# SparkFun_MicroMod_Function_ADIN1110.net
KiCad netlist of a schematic drawn in EAGLE
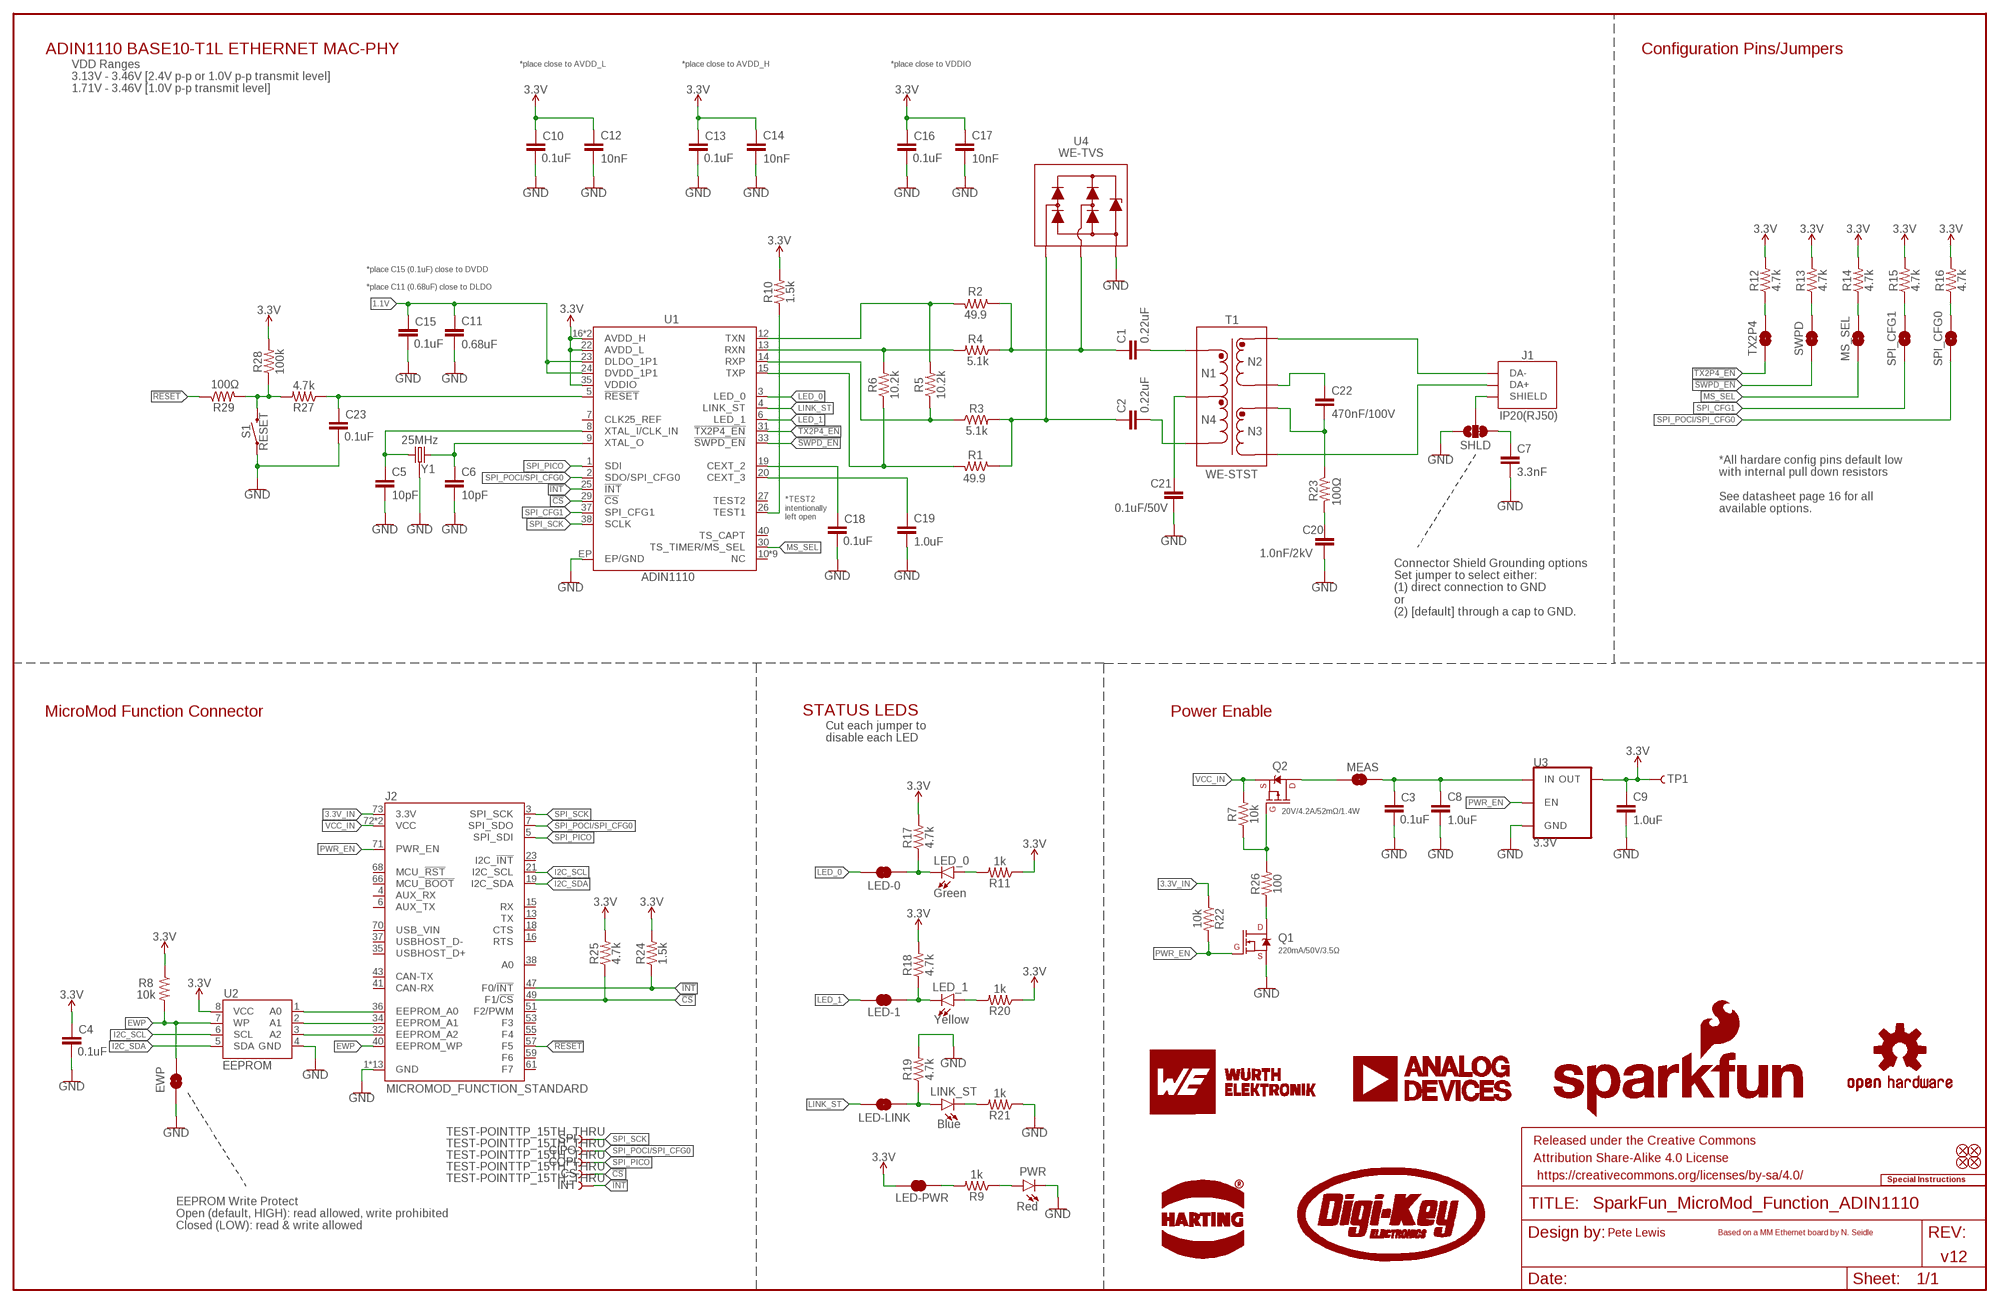
[diagram p0: schematic, sheet 1]

(export (version "E")
  (design (tool "Eeschema 10.0.6"))
  (components
    (comp (ref "C1")
      (value "0.22uF")
      (footprint "eagle-import:0603")
      (libsource (lib "eagle-import") (part "0.22UF-0603-50V-10%"))
    )
    (comp (ref "C2")
      (value "0.22uF")
      (footprint "eagle-import:0603")
      (libsource (lib "eagle-import") (part "0.22UF-0603-50V-10%"))
    )
    (comp (ref "C3")
      (value "0.1uF")
      (footprint "eagle-import:0603")
      (libsource (lib "eagle-import") (part "0.1UF-0603-25V-10%-X7R-WE"))
    )
    (comp (ref "C4")
      (value "0.1uF")
      (footprint "eagle-import:0603")
      (libsource (lib "eagle-import") (part "0.1UF-0603-25V-10%-X7R-WE"))
    )
    (comp (ref "C5")
      (value "10pF")
      (footprint "eagle-import:0603")
      (libsource (lib "eagle-import") (part "10PF-0603-50V-5%-C0G-WE"))
    )
    (comp (ref "C6")
      (value "10pF")
      (footprint "eagle-import:0603")
      (libsource (lib "eagle-import") (part "10PF-0603-50V-5%-C0G-WE"))
    )
    (comp (ref "C7")
      (value "3.3nF")
      (footprint "eagle-import:0603")
      (libsource (lib "eagle-import") (part "3.3NF-0603-100V-10%-WE"))
    )
    (comp (ref "C8")
      (value "1.0uF")
      (footprint "eagle-import:0603")
      (libsource (lib "eagle-import") (part "1.0UF-0603-16V-10%-X7R-WE"))
    )
    (comp (ref "C9")
      (value "1.0uF")
      (footprint "eagle-import:0603")
      (libsource (lib "eagle-import") (part "1.0UF-0603-16V-10%-X7R-WE"))
    )
    (comp (ref "C10")
      (value "0.1uF")
      (footprint "eagle-import:0402-TIGHT")
      (libsource (lib "eagle-import") (part "0.1UF-0402T-16V-10%-X7R-WE"))
    )
    (comp (ref "C11")
      (value "0.68uF")
      (footprint "eagle-import:0603")
      (libsource (lib "eagle-import") (part "0.68UF-0603-16V-10%-X7R-WE"))
    )
    (comp (ref "C12")
      (value "10nF")
      (footprint "eagle-import:0402-TIGHT")
      (libsource (lib "eagle-import") (part "10NF-0402T-25V-10%-X7R-WE"))
    )
    (comp (ref "C13")
      (value "0.1uF")
      (footprint "eagle-import:0402-TIGHT")
      (libsource (lib "eagle-import") (part "0.1UF-0402T-16V-10%-X7R-WE"))
    )
    (comp (ref "C14")
      (value "10nF")
      (footprint "eagle-import:0402-TIGHT")
      (libsource (lib "eagle-import") (part "10NF-0402T-25V-10%-X7R-WE"))
    )
    (comp (ref "C15")
      (value "0.1uF")
      (footprint "eagle-import:0402-TIGHT")
      (libsource (lib "eagle-import") (part "0.1UF-0402T-16V-10%-X7R-WE"))
    )
    (comp (ref "C16")
      (value "0.1uF")
      (footprint "eagle-import:0402-TIGHT")
      (libsource (lib "eagle-import") (part "0.1UF-0402T-16V-10%-X7R-WE"))
    )
    (comp (ref "C17")
      (value "10nF")
      (footprint "eagle-import:0402-TIGHT")
      (libsource (lib "eagle-import") (part "10NF-0402T-25V-10%-X7R-WE"))
    )
    (comp (ref "C18")
      (value "0.1uF")
      (footprint "eagle-import:0402-TIGHT")
      (libsource (lib "eagle-import") (part "0.1UF-0402T-16V-10%-X7R-WE"))
    )
    (comp (ref "C19")
      (value "1.0uF")
      (footprint "eagle-import:0402-TIGHT")
      (libsource (lib "eagle-import") (part "1.0UF-0402T-16V-10%"))
    )
    (comp (ref "C20")
      (value "1.0nF/2kV")
      (footprint "eagle-import:1206")
      (libsource (lib "eagle-import") (part "1.0NF/1000PF-1206-2KV-10%-X7R-WORTH-ELEKRONIK"))
    )
    (comp (ref "C21")
      (value "0.1uF/50V")
      (footprint "eagle-import:0603")
      (libsource (lib "eagle-import") (part "0.1UF-0603-50V-10%-X7R-WE"))
    )
    (comp (ref "C22")
      (value "470nF/100V")
      (footprint "eagle-import:0805")
      (libsource (lib "eagle-import") (part "470NF-0805-100V-10%-X7S"))
    )
    (comp (ref "C23")
      (value "0.1uF")
      (footprint "eagle-import:0402-TIGHT")
      (libsource (lib "eagle-import") (part "0.1UF-0402T-16V-10%-X7R-WE"))
    )
    (comp (ref "CIPO")
      (value "TEST-POINTTP_15TH_THRU")
      (footprint "eagle-import:TP_15TH")
      (libsource (lib "eagle-import") (part "TEST-POINTTP_15TH_THRU"))
    )
    (comp (ref "COPI")
      (value "TEST-POINTTP_15TH_THRU")
      (footprint "eagle-import:TP_15TH")
      (libsource (lib "eagle-import") (part "TEST-POINTTP_15TH_THRU"))
    )
    (comp (ref "CS")
      (value "TEST-POINTTP_15TH_THRU")
      (footprint "eagle-import:TP_15TH")
      (libsource (lib "eagle-import") (part "TEST-POINTTP_15TH_THRU"))
    )
    (comp (ref "EWP")
      (value "JUMPER-SMT_2_NO_SILK")
      (footprint "eagle-import:SMT-JUMPER_2_NO_SILK")
      (libsource (lib "eagle-import") (part "JUMPER-SMT_2_NO_SILK"))
    )
    (comp (ref "FD1")
      (value "FIDUCIALUFIDUCIAL")
      (footprint "eagle-import:FIDUCIAL-MICRO")
      (libsource (lib "eagle-import") (part "FIDUCIALUFIDUCIAL"))
    )
    (comp (ref "FD2")
      (value "FIDUCIALUFIDUCIAL")
      (footprint "eagle-import:FIDUCIAL-MICRO")
      (libsource (lib "eagle-import") (part "FIDUCIALUFIDUCIAL"))
    )
    (comp (ref "FD3")
      (value "FIDUCIALUFIDUCIAL")
      (footprint "eagle-import:FIDUCIAL-MICRO")
      (libsource (lib "eagle-import") (part "FIDUCIALUFIDUCIAL"))
    )
    (comp (ref "FD4")
      (value "FIDUCIALUFIDUCIAL")
      (footprint "eagle-import:FIDUCIAL-MICRO")
      (libsource (lib "eagle-import") (part "FIDUCIALUFIDUCIAL"))
    )
    (comp (ref "FRAME1")
      (value "FRAME-LEDGER")
      (footprint "eagle-import:CREATIVE_COMMONS")
      (libsource (lib "eagle-import") (part "FRAME-LEDGER"))
    )
    (comp (ref "INT")
      (value "TEST-POINTTP_15TH_THRU")
      (footprint "eagle-import:TP_15TH")
      (libsource (lib "eagle-import") (part "TEST-POINTTP_15TH_THRU"))
    )
    (comp (ref "J1")
      (value "IP20(RJ50)")
      (footprint "eagle-import:T1_INDUSTRIAL_JACK_AH_IP20")
      (libsource (lib "eagle-import") (part "T1_INDUSTRIAL_JACK_AH_IP20"))
    )
    (comp (ref "J2")
      (value "MICROMOD_FUNCTION_STANDARD")
      (footprint "eagle-import:M.2-CARD-E-22_FUNCTION_STANDARD")
      (libsource (lib "eagle-import") (part "MICROMOD_FUNCTION_STANDARD"))
    )
    (comp (ref "LED-0")
      (value "JUMPER-SMT_2_NC_TRACE_SILK")
      (footprint "eagle-import:SMT-JUMPER_2_NC_TRACE_SILK")
      (libsource (lib "eagle-import") (part "JUMPER-SMT_2_NC_TRACE_SILK"))
    )
    (comp (ref "LED-1")
      (value "JUMPER-SMT_2_NC_TRACE_SILK")
      (footprint "eagle-import:SMT-JUMPER_2_NC_TRACE_SILK")
      (libsource (lib "eagle-import") (part "JUMPER-SMT_2_NC_TRACE_SILK"))
    )
    (comp (ref "LED-LINK")
      (value "JUMPER-SMT_2_NC_TRACE_SILK")
      (footprint "eagle-import:SMT-JUMPER_2_NC_TRACE_SILK")
      (libsource (lib "eagle-import") (part "JUMPER-SMT_2_NC_TRACE_SILK"))
    )
    (comp (ref "LED-PWR")
      (value "JUMPER-SMT_2_NC_TRACE_SILK")
      (footprint "eagle-import:SMT-JUMPER_2_NC_TRACE_SILK")
      (libsource (lib "eagle-import") (part "JUMPER-SMT_2_NC_TRACE_SILK"))
    )
    (comp (ref "LED_0")
      (value "Green")
      (footprint "eagle-import:LED-0603")
      (libsource (lib "eagle-import") (part "LED-GREEN-0603-WE"))
    )
    (comp (ref "LED_1")
      (value "Yellow")
      (footprint "eagle-import:LED-0603")
      (libsource (lib "eagle-import") (part "LED-YELLOW-0603-WE"))
    )
    (comp (ref "LINK_ST")
      (value "Blue")
      (footprint "eagle-import:LED-0603")
      (libsource (lib "eagle-import") (part "LED-BLUE-0603-WE"))
    )
    (comp (ref "LOGO1")
      (value "SFE_LOGO_NAME_FLAME.1_INCH")
      (footprint "eagle-import:SFE_LOGO_NAME_FLAME_.1")
      (libsource (lib "eagle-import") (part "SFE_LOGO_NAME_FLAME.1_INCH"))
    )
    (comp (ref "LOGO2")
      (value "SPECIAL_INSTRUCTIONS-ORDERING")
      (footprint "eagle-import:ORDERING_INSTRUCTIONS")
      (libsource (lib "eagle-import") (part "SPECIAL_INSTRUCTIONS-ORDERING"))
    )
    (comp (ref "LOGO3")
      (value "OSHW-LOGOMINI")
      (footprint "eagle-import:OSHW-LOGO-MINI")
      (libsource (lib "eagle-import") (part "OSHW-LOGOMINI"))
    )
    (comp (ref "MEAS")
      (value "JUMPER-COMBO_2_NC_TRACE")
      (footprint "eagle-import:COMBO-JUMPER_2_NC_TRACE")
      (libsource (lib "eagle-import") (part "JUMPER-COMBO_2_NC_TRACE"))
    )
    (comp (ref "MS_SEL")
      (value "JUMPER-SMT_2_NO_SILK")
      (footprint "eagle-import:SMT-JUMPER_2_NO_SILK")
      (libsource (lib "eagle-import") (part "JUMPER-SMT_2_NO_SILK"))
    )
    (comp (ref "PWR")
      (value "Red")
      (footprint "eagle-import:LED-0603")
      (libsource (lib "eagle-import") (part "LED-RED-0603-WE"))
    )
    (comp (ref "Q1")
      (value "220mA/50V/3.5Ω")
      (footprint "eagle-import:SOT23-3")
      (libsource (lib "eagle-import") (part "MOSFET-NCH-BSS138"))
    )
    (comp (ref "Q2")
      (value "20V/4.2A/52mΩ/1.4W")
      (footprint "eagle-import:SOT23-3")
      (libsource (lib "eagle-import") (part "MOSFET_PCH-DMG2305UX-7"))
    )
    (comp (ref "R1")
      (value "49.9")
      (footprint "eagle-import:0603")
      (libsource (lib "eagle-import") (part "49.9OHM-0603-1/10W-1%"))
    )
    (comp (ref "R2")
      (value "49.9")
      (footprint "eagle-import:0603")
      (libsource (lib "eagle-import") (part "49.9OHM-0603-1/10W-1%"))
    )
    (comp (ref "R3")
      (value "5.1k")
      (footprint "eagle-import:0402-TIGHT")
      (libsource (lib "eagle-import") (part "5.1KOHM-0402T-1/16W-1%"))
    )
    (comp (ref "R4")
      (value "5.1k")
      (footprint "eagle-import:0402-TIGHT")
      (libsource (lib "eagle-import") (part "5.1KOHM-0402T-1/16W-1%"))
    )
    (comp (ref "R5")
      (value "10.2k")
      (footprint "eagle-import:0402-TIGHT")
      (libsource (lib "eagle-import") (part "10.2KOHM-0402-1/16W-1%"))
    )
    (comp (ref "R6")
      (value "10.2k")
      (footprint "eagle-import:0402-TIGHT")
      (libsource (lib "eagle-import") (part "10.2KOHM-0402-1/16W-1%"))
    )
    (comp (ref "R7")
      (value "10k")
      (footprint "eagle-import:0603")
      (libsource (lib "eagle-import") (part "10KOHM-0603-1/10W-1%"))
    )
    (comp (ref "R8")
      (value "10k")
      (footprint "eagle-import:0603")
      (libsource (lib "eagle-import") (part "10KOHM-0603-1/10W-1%"))
    )
    (comp (ref "R9")
      (value "1k")
      (footprint "eagle-import:0402-TIGHT")
      (libsource (lib "eagle-import") (part "1KOHM-0402T-1/16W-1%"))
    )
    (comp (ref "R10")
      (value "1.5k")
      (footprint "eagle-import:0603")
      (libsource (lib "eagle-import") (part "1.5KOHM-0603-1/10W-1%"))
    )
    (comp (ref "R11")
      (value "1k")
      (footprint "eagle-import:0402-TIGHT")
      (libsource (lib "eagle-import") (part "1KOHM-0402T-1/16W-1%"))
    )
    (comp (ref "R12")
      (value "4.7k")
      (footprint "eagle-import:0402-TIGHT")
      (libsource (lib "eagle-import") (part "4.7KOHM-0402T-1/16W-1%"))
    )
    (comp (ref "R13")
      (value "4.7k")
      (footprint "eagle-import:0402-TIGHT")
      (libsource (lib "eagle-import") (part "4.7KOHM-0402T-1/16W-1%"))
    )
    (comp (ref "R14")
      (value "4.7k")
      (footprint "eagle-import:0402-TIGHT")
      (libsource (lib "eagle-import") (part "4.7KOHM-0402T-1/16W-1%"))
    )
    (comp (ref "R15")
      (value "4.7k")
      (footprint "eagle-import:0402-TIGHT")
      (libsource (lib "eagle-import") (part "4.7KOHM-0402T-1/16W-1%"))
    )
    (comp (ref "R16")
      (value "4.7k")
      (footprint "eagle-import:0402-TIGHT")
      (libsource (lib "eagle-import") (part "4.7KOHM-0402T-1/16W-1%"))
    )
    (comp (ref "R17")
      (value "4.7k")
      (footprint "eagle-import:0402-TIGHT")
      (libsource (lib "eagle-import") (part "4.7KOHM-0402T-1/16W-1%"))
    )
    (comp (ref "R18")
      (value "4.7k")
      (footprint "eagle-import:0402-TIGHT")
      (libsource (lib "eagle-import") (part "4.7KOHM-0402T-1/16W-1%"))
    )
    (comp (ref "R19")
      (value "4.7k")
      (footprint "eagle-import:0402-TIGHT")
      (libsource (lib "eagle-import") (part "4.7KOHM-0402T-1/16W-1%"))
    )
    (comp (ref "R20")
      (value "1k")
      (footprint "eagle-import:0402-TIGHT")
      (libsource (lib "eagle-import") (part "1KOHM-0402T-1/16W-1%"))
    )
    (comp (ref "R21")
      (value "1k")
      (footprint "eagle-import:0402-TIGHT")
      (libsource (lib "eagle-import") (part "1KOHM-0402T-1/16W-1%"))
    )
    (comp (ref "R22")
      (value "10k")
      (footprint "eagle-import:0603")
      (libsource (lib "eagle-import") (part "10KOHM-0603-1/10W-1%"))
    )
    (comp (ref "R23")
      (value "100Ω")
      (footprint "eagle-import:0603")
      (libsource (lib "eagle-import") (part "100OHM-0603-1/10W-1%"))
    )
    (comp (ref "R24")
      (value "1.5k")
      (footprint "eagle-import:0603")
      (libsource (lib "eagle-import") (part "1.5KOHM-0603-1/10W-1%"))
    )
    (comp (ref "R25")
      (value "4.7k")
      (footprint "eagle-import:0402-TIGHT")
      (libsource (lib "eagle-import") (part "4.7KOHM-0402T-1/16W-1%"))
    )
    (comp (ref "R26")
      (value "100")
      (footprint "eagle-import:0603")
      (libsource (lib "eagle-import") (part "100OHM-0603-1/10W-1%"))
    )
    (comp (ref "R27")
      (value "4.7k")
      (footprint "eagle-import:0603")
      (libsource (lib "eagle-import") (part "4.7KOHM-0603-1/10W-1%"))
    )
    (comp (ref "R28")
      (value "100k")
      (footprint "eagle-import:0402-TIGHT")
      (libsource (lib "eagle-import") (part "100KOHM-0402T-1/16W-1%"))
    )
    (comp (ref "R29")
      (value "100Ω")
      (footprint "eagle-import:0603")
      (libsource (lib "eagle-import") (part "100OHM-0603-1/10W-1%"))
    )
    (comp (ref "S1")
      (value "RESET")
      (footprint "eagle-import:TACTILE_SWITCH_SMD_5.2MM")
      (libsource (lib "eagle-import") (part "MOMENTARY-SWITCH-SPST-SMD-5.2MM-TALL"))
    )
    (comp (ref "SHLD")
      (value "JUMPER-SMT_3_1-NC_TRACE_SILK")
      (footprint "eagle-import:SMT-JUMPER_3_1-NC_TRACE_SILK")
      (libsource (lib "eagle-import") (part "JUMPER-SMT_3_1-NC_TRACE_SILK"))
    )
    (comp (ref "SPI")
      (value "TEST-POINTTP_15TH_THRU")
      (footprint "eagle-import:TP_15TH")
      (libsource (lib "eagle-import") (part "TEST-POINTTP_15TH_THRU"))
    )
    (comp (ref "SPI_CFG0")
      (value "JUMPER-SMT_2_NO_SILK")
      (footprint "eagle-import:SMT-JUMPER_2_NO_SILK")
      (libsource (lib "eagle-import") (part "JUMPER-SMT_2_NO_SILK"))
    )
    (comp (ref "SPI_CFG1")
      (value "JUMPER-SMT_2_NO_SILK")
      (footprint "eagle-import:SMT-JUMPER_2_NO_SILK")
      (libsource (lib "eagle-import") (part "JUMPER-SMT_2_NO_SILK"))
    )
    (comp (ref "SWPD")
      (value "JUMPER-SMT_2_NO_SILK")
      (footprint "eagle-import:SMT-JUMPER_2_NO_SILK")
      (libsource (lib "eagle-import") (part "JUMPER-SMT_2_NO_SILK"))
    )
    (comp (ref "T1")
      (value "WE-STST")
      (footprint "eagle-import:WE_STST_TRANSFORMER_1_1_SMD_3.2X4.7MM_74930030")
      (libsource (lib "eagle-import") (part "WE_STST_TRANSFORMER_1{colon}1_SMD_74930030_3.2X4.7MM"))
    )
    (comp (ref "TP1")
      (value "TEST-POINT3X4")
      (footprint "eagle-import:PAD.03X.04")
      (libsource (lib "eagle-import") (part "TEST-POINT3X4"))
    )
    (comp (ref "TX2P4")
      (value "JUMPER-SMT_2_NO_SILK")
      (footprint "eagle-import:SMT-JUMPER_2_NO_SILK")
      (libsource (lib "eagle-import") (part "JUMPER-SMT_2_NO_SILK"))
    )
    (comp (ref "U$2")
      (value "HARTING_LOGO")
      (footprint "eagle-import:HARTING_LOGO_9MM")
      (libsource (lib "eagle-import") (part "HARTING_LOGO"))
    )
    (comp (ref "U$5")
      (value "DIGIKEY_LOGO")
      (footprint "eagle-import:DIGIKEY_LOGO")
      (libsource (lib "eagle-import") (part "DIGIKEY_LOGO"))
    )
    (comp (ref "U$19")
      (value "WURTH_LOGO")
      (footprint "eagle-import:WURTH_LOGO_9MM")
      (libsource (lib "eagle-import") (part "WURTH_LOGO"))
    )
    (comp (ref "U$33")
      (value "ANALOG_DEVICES_LOGO")
      (footprint "eagle-import:ANALOG_DEVICE_LOGO_9MM")
      (libsource (lib "eagle-import") (part "ANALOG_DEVICES_LOGO"))
    )
    (comp (ref "U1")
      (value "ADIN1110")
      (footprint "eagle-import:LFCSP-40")
      (libsource (lib "eagle-import") (part "ADIN1110"))
    )
    (comp (ref "U2")
      (value "EEPROM")
      (footprint "eagle-import:SO08")
      (libsource (lib "eagle-import") (part "EEPROM-I2C512K"))
    )
    (comp (ref "U3")
      (value "3.3V")
      (footprint "eagle-import:SOT23-5")
      (libsource (lib "eagle-import") (part "V_REG_AP2112K-3.3V"))
    )
    (comp (ref "U4")
      (value "WE-TVS")
      (footprint "eagle-import:WE_TVS_1.0X1.2MM")
      (libsource (lib "eagle-import") (part "WE-TVS_DIODE_ARRAY_824012823_1.0X1.2MM"))
    )
    (comp (ref "Y1")
      (value "25MHz")
      (footprint "eagle-import:CRYSTAL-SMD-2.0X1.6MM-WE")
      (libsource (lib "eagle-import") (part "CRYSTAL-25MHZ-WE-SMD-2.0X1.6MM-WE"))
    )
  )
  (nets
    (net (code "1") (name "/~{CS}") (class "Default")
      (node (ref "CS") (pin "1") (pinfunction "1_1") (pintype "bidirectional"))
      (node (ref "J2") (pin "49") (pinfunction "F1/~{CS}_49") (pintype "bidirectional"))
      (node (ref "R25") (pin "1") (pinfunction "1_1") (pintype "passive"))
      (node (ref "U1") (pin "29") (pinfunction "~{CS}_29") (pintype "bidirectional"))
    )
    (net (code "2") (name "/~{INT}") (class "Default")
      (node (ref "INT") (pin "1") (pinfunction "1_1") (pintype "bidirectional"))
      (node (ref "J2") (pin "47") (pinfunction "F0/~{INT}_47") (pintype "bidirectional"))
      (node (ref "R24") (pin "1") (pinfunction "1_1") (pintype "passive"))
      (node (ref "U1") (pin "25") (pinfunction "~{INT}_25") (pintype "bidirectional"))
    )
    (net (code "3") (name "/~{RESET}") (class "Default")
      (node (ref "J2") (pin "57") (pinfunction "F5_57") (pintype "bidirectional"))
      (node (ref "R29") (pin "1") (pinfunction "1_1") (pintype "passive"))
    )
    (net (code "4") (name "/~{SWPD_EN}") (class "Default")
      (node (ref "SWPD") (pin "1") (pinfunction "1_1") (pintype "passive"))
      (node (ref "U1") (pin "33") (pinfunction "~{SWPD_EN}_33") (pintype "bidirectional"))
    )
    (net (code "5") (name "/~{TX2P4_EN}") (class "Default")
      (node (ref "TX2P4") (pin "1") (pinfunction "1_1") (pintype "passive"))
      (node (ref "U1") (pin "31") (pinfunction "~{TX2P4_EN}_31") (pintype "bidirectional"))
    )
    (net (code "6") (name "1.1V") (class "Default")
      (node (ref "C11") (pin "1") (pinfunction "1_1") (pintype "passive"))
      (node (ref "C15") (pin "1") (pinfunction "1_1") (pintype "passive"))
      (node (ref "U1") (pin "23") (pinfunction "DLDO_1P1_23") (pintype "bidirectional"))
      (node (ref "U1") (pin "24") (pinfunction "DVDD_1P1_24") (pintype "bidirectional"))
    )
    (net (code "7") (name "3.3V") (class "Default")
      (node (ref "C10") (pin "1") (pinfunction "1_1") (pintype "passive"))
      (node (ref "C12") (pin "1") (pinfunction "1_1") (pintype "passive"))
      (node (ref "C13") (pin "1") (pinfunction "1_1") (pintype "passive"))
      (node (ref "C14") (pin "1") (pinfunction "1_1") (pintype "passive"))
      (node (ref "C16") (pin "1") (pinfunction "1_1") (pintype "passive"))
      (node (ref "C17") (pin "1") (pinfunction "1_1") (pintype "passive"))
      (node (ref "C4") (pin "1") (pinfunction "1_1") (pintype "passive"))
      (node (ref "C9") (pin "1") (pinfunction "1_1") (pintype "passive"))
      (node (ref "LED-PWR") (pin "2") (pinfunction "2_2") (pintype "passive"))
      (node (ref "R10") (pin "2") (pinfunction "2_2") (pintype "passive"))
      (node (ref "R11") (pin "1") (pinfunction "1_1") (pintype "passive"))
      (node (ref "R12") (pin "2") (pinfunction "2_2") (pintype "passive"))
      (node (ref "R13") (pin "2") (pinfunction "2_2") (pintype "passive"))
      (node (ref "R14") (pin "2") (pinfunction "2_2") (pintype "passive"))
      (node (ref "R15") (pin "2") (pinfunction "2_2") (pintype "passive"))
      (node (ref "R16") (pin "2") (pinfunction "2_2") (pintype "passive"))
      (node (ref "R17") (pin "2") (pinfunction "2_2") (pintype "passive"))
      (node (ref "R18") (pin "2") (pinfunction "2_2") (pintype "passive"))
      (node (ref "R20") (pin "1") (pinfunction "1_1") (pintype "passive"))
      (node (ref "R24") (pin "2") (pinfunction "2_2") (pintype "passive"))
      (node (ref "R25") (pin "2") (pinfunction "2_2") (pintype "passive"))
      (node (ref "R28") (pin "2") (pinfunction "2_2") (pintype "passive"))
      (node (ref "R8") (pin "1") (pinfunction "1_1") (pintype "passive"))
      (node (ref "TP1") (pin "1") (pinfunction "1_1") (pintype "bidirectional"))
      (node (ref "U1") (pin "16") (pinfunction "AVDD_H_16") (pintype "bidirectional"))
      (node (ref "U1") (pin "17") (pinfunction "AVDD_H_17") (pintype "bidirectional"))
      (node (ref "U1") (pin "22") (pinfunction "AVDD_L_22") (pintype "bidirectional"))
      (node (ref "U1") (pin "35") (pinfunction "VDDIO_35") (pintype "bidirectional"))
      (node (ref "U2") (pin "8") (pinfunction "VCC_8") (pintype "power_in"))
      (node (ref "U3") (pin "5") (pinfunction "OUT_5") (pintype "passive"))
    )
    (net (code "8") (name "3.3V_IN") (class "Default")
      (node (ref "J2") (pin "73") (pinfunction "3.3V_73") (pintype "bidirectional"))
      (node (ref "R22") (pin "1") (pinfunction "1_1") (pintype "passive"))
    )
    (net (code "9") (name "EWP") (class "Default")
      (node (ref "EWP") (pin "2") (pinfunction "2_2") (pintype "passive"))
      (node (ref "J2") (pin "40") (pinfunction "EEPROM_WP_40") (pintype "bidirectional"))
      (node (ref "R8") (pin "2") (pinfunction "2_2") (pintype "passive"))
      (node (ref "U2") (pin "7") (pinfunction "WP_7") (pintype "bidirectional"))
    )
    (net (code "10") (name "GND") (class "Default")
      (node (ref "C10") (pin "2") (pinfunction "2_2") (pintype "passive"))
      (node (ref "C11") (pin "2") (pinfunction "2_2") (pintype "passive"))
      (node (ref "C12") (pin "2") (pinfunction "2_2") (pintype "passive"))
      (node (ref "C13") (pin "2") (pinfunction "2_2") (pintype "passive"))
      (node (ref "C14") (pin "2") (pinfunction "2_2") (pintype "passive"))
      (node (ref "C15") (pin "2") (pinfunction "2_2") (pintype "passive"))
      (node (ref "C16") (pin "2") (pinfunction "2_2") (pintype "passive"))
      (node (ref "C17") (pin "2") (pinfunction "2_2") (pintype "passive"))
      (node (ref "C18") (pin "2") (pinfunction "2_2") (pintype "passive"))
      (node (ref "C19") (pin "2") (pinfunction "2_2") (pintype "passive"))
      (node (ref "C20") (pin "2") (pinfunction "2_2") (pintype "passive"))
      (node (ref "C21") (pin "2") (pinfunction "2_2") (pintype "passive"))
      (node (ref "C23") (pin "2") (pinfunction "2_2") (pintype "passive"))
      (node (ref "C3") (pin "2") (pinfunction "2_2") (pintype "passive"))
      (node (ref "C4") (pin "2") (pinfunction "2_2") (pintype "passive"))
      (node (ref "C5") (pin "2") (pinfunction "2_2") (pintype "passive"))
      (node (ref "C6") (pin "2") (pinfunction "2_2") (pintype "passive"))
      (node (ref "C7") (pin "2") (pinfunction "2_2") (pintype "passive"))
      (node (ref "C8") (pin "2") (pinfunction "2_2") (pintype "passive"))
      (node (ref "C9") (pin "2") (pinfunction "2_2") (pintype "passive"))
      (node (ref "EWP") (pin "1") (pinfunction "1_1") (pintype "passive"))
      (node (ref "J2") (pin "1") (pinfunction "GND_1") (pintype "bidirectional"))
      (node (ref "J2") (pin "2") (pinfunction "GND_2") (pintype "bidirectional"))
      (node (ref "J2") (pin "33") (pinfunction "GND_33") (pintype "bidirectional"))
      (node (ref "J2") (pin "39") (pinfunction "GND_39") (pintype "bidirectional"))
      (node (ref "J2") (pin "45") (pinfunction "GND_45") (pintype "bidirectional"))
      (node (ref "J2") (pin "75") (pinfunction "GND_75") (pintype "bidirectional"))
      (node (ref "J2") (pin "8") (pinfunction "GND_8") (pintype "bidirectional"))
      (node (ref "J2") (pin "GND1") (pinfunction "GND_GND1") (pintype "bidirectional"))
      (node (ref "J2") (pin "GND2") (pinfunction "GND_GND2") (pintype "bidirectional"))
      (node (ref "J2") (pin "GND3") (pinfunction "GND_GND3") (pintype "bidirectional"))
      (node (ref "J2") (pin "GND4") (pinfunction "GND_GND4") (pintype "bidirectional"))
      (node (ref "J2") (pin "GND5") (pinfunction "GND_GND5") (pintype "bidirectional"))
      (node (ref "J2") (pin "GND6") (pinfunction "GND_GND6") (pintype "bidirectional"))
      (node (ref "PWR") (pin "C") (pinfunction "C_C") (pintype "passive"))
      (node (ref "Q1") (pin "2") (pinfunction "S_2") (pintype "bidirectional"))
      (node (ref "R19") (pin "2") (pinfunction "2_2") (pintype "passive"))
      (node (ref "R21") (pin "1") (pinfunction "1_1") (pintype "passive"))
      (node (ref "S1") (pin "1") (pinfunction "1_1") (pintype "passive"))
      (node (ref "SHLD") (pin "1") (pinfunction "1_1") (pintype "passive"))
      (node (ref "U1") (pin "EP") (pinfunction "EP/GND_EP") (pintype "bidirectional"))
      (node (ref "U2") (pin "4") (pinfunction "GND_4") (pintype "power_in"))
      (node (ref "U3") (pin "2") (pinfunction "GND_2") (pintype "input"))
      (node (ref "U4") (pin "3") (pinfunction "3_3") (pintype "bidirectional"))
      (node (ref "Y1") (pin "2") (pinfunction "GND_2") (pintype "power_in"))
      (node (ref "Y1") (pin "4") (pinfunction "GND_4") (pintype "power_in"))
    )
    (net (code "11") (name "I2C_SCL") (class "Default")
      (node (ref "J2") (pin "21") (pinfunction "I2C_SCL_21") (pintype "bidirectional"))
      (node (ref "U2") (pin "6") (pinfunction "SCL_6") (pintype "bidirectional"))
    )
    (net (code "12") (name "I2C_SDA") (class "Default")
      (node (ref "J2") (pin "19") (pinfunction "I2C_SDA_19") (pintype "bidirectional"))
      (node (ref "U2") (pin "5") (pinfunction "SDA_5") (pintype "bidirectional"))
    )
    (net (code "13") (name "LED_0") (class "Default")
      (node (ref "LED-0") (pin "2") (pinfunction "2_2") (pintype "passive"))
      (node (ref "U1") (pin "3") (pinfunction "LED_0_3") (pintype "bidirectional"))
    )
    (net (code "14") (name "LED_1") (class "Default")
      (node (ref "LED-1") (pin "2") (pinfunction "2_2") (pintype "passive"))
      (node (ref "U1") (pin "6") (pinfunction "LED_1_6") (pintype "bidirectional"))
    )
    (net (code "15") (name "LINK_ST") (class "Default")
      (node (ref "LED-LINK") (pin "2") (pinfunction "2_2") (pintype "passive"))
      (node (ref "U1") (pin "4") (pinfunction "LINK_ST_4") (pintype "bidirectional"))
    )
    (net (code "16") (name "MS_SEL") (class "Default")
      (node (ref "MS_SEL") (pin "1") (pinfunction "1_1") (pintype "passive"))
      (node (ref "U1") (pin "30") (pinfunction "TS_TIMER/MS_SEL_30") (pintype "bidirectional"))
    )
    (net (code "17") (name "Net-(C1-Pad1)") (class "Default")
      (node (ref "C1") (pin "1") (pinfunction "1_1") (pintype "passive"))
      (node (ref "R2") (pin "1") (pinfunction "1_1") (pintype "passive"))
      (node (ref "R4") (pin "1") (pinfunction "1_1") (pintype "passive"))
      (node (ref "U4") (pin "2") (pinfunction "2_2") (pintype "bidirectional"))
      (node (ref "U4") (pin "5") (pinfunction "2_5") (pintype "bidirectional"))
    )
    (net (code "18") (name "Net-(C1-Pad2)") (class "Default")
      (node (ref "C1") (pin "2") (pinfunction "2_2") (pintype "passive"))
      (node (ref "T1") (pin "1") (pinfunction "1_1") (pintype "bidirectional"))
    )
    (net (code "19") (name "Net-(C2-Pad1)") (class "Default")
      (node (ref "C2") (pin "1") (pinfunction "1_1") (pintype "passive"))
      (node (ref "R1") (pin "1") (pinfunction "1_1") (pintype "passive"))
      (node (ref "R3") (pin "2") (pinfunction "2_2") (pintype "passive"))
      (node (ref "U4") (pin "1") (pinfunction "1_1") (pintype "bidirectional"))
      (node (ref "U4") (pin "6") (pinfunction "1_6") (pintype "bidirectional"))
    )
    (net (code "20") (name "Net-(C2-Pad2)") (class "Default")
      (node (ref "C2") (pin "2") (pinfunction "2_2") (pintype "passive"))
      (node (ref "T1") (pin "2") (pinfunction "2_2") (pintype "bidirectional"))
    )
    (net (code "21") (name "Net-(C7-Pad1)") (class "Default")
      (node (ref "C7") (pin "1") (pinfunction "1_1") (pintype "passive"))
      (node (ref "SHLD") (pin "3") (pinfunction "3_3") (pintype "passive"))
    )
    (net (code "22") (name "Net-(C20-Pad1)") (class "Default")
      (node (ref "C20") (pin "1") (pinfunction "1_1") (pintype "passive"))
      (node (ref "R23") (pin "2") (pinfunction "2_2") (pintype "passive"))
    )
    (net (code "23") (name "Net-(C21-Pad1)") (class "Default")
      (node (ref "C21") (pin "1") (pinfunction "1_1") (pintype "passive"))
      (node (ref "T1") (pin "5") (pinfunction "5_5") (pintype "bidirectional"))
    )
    (net (code "24") (name "Net-(C22-Pad1)") (class "Default")
      (node (ref "C22") (pin "1") (pinfunction "1_1") (pintype "passive"))
      (node (ref "T1") (pin "4") (pinfunction "4_4") (pintype "bidirectional"))
    )
    (net (code "25") (name "Net-(C22-Pad2)") (class "Default")
      (node (ref "C22") (pin "2") (pinfunction "2_2") (pintype "passive"))
      (node (ref "R23") (pin "1") (pinfunction "1_1") (pintype "passive"))
      (node (ref "T1") (pin "3") (pinfunction "3_3") (pintype "bidirectional"))
    )
    (net (code "26") (name "Net-(J1-DA+)") (class "Default")
      (node (ref "J1") (pin "1") (pinfunction "DA+_1") (pintype "passive"))
      (node (ref "T1") (pin "7") (pinfunction "7_7") (pintype "bidirectional"))
    )
    (net (code "27") (name "Net-(J1-DA-)") (class "Default")
      (node (ref "J1") (pin "2") (pinfunction "DA-_2") (pintype "passive"))
      (node (ref "T1") (pin "6") (pinfunction "6_6") (pintype "bidirectional"))
    )
    (net (code "28") (name "Net-(J1-SHIELD-PadS1)") (class "Default")
      (node (ref "J1") (pin "S1") (pinfunction "SHIELD_S1") (pintype "passive"))
      (node (ref "J1") (pin "S2") (pinfunction "SHIELD_S2") (pintype "passive"))
      (node (ref "J1") (pin "S3") (pinfunction "SHIELD_S3") (pintype "passive"))
      (node (ref "J1") (pin "S4") (pinfunction "SHIELD_S4") (pintype "passive"))
      (node (ref "SHLD") (pin "2") (pinfunction "2_2") (pintype "passive"))
    )
    (net (code "29") (name "Net-(J2-EEPROM_A0)") (class "Default")
      (node (ref "J2") (pin "36") (pinfunction "EEPROM_A0_36") (pintype "bidirectional"))
      (node (ref "U2") (pin "1") (pinfunction "A0_1") (pintype "bidirectional"))
    )
    (net (code "30") (name "Net-(J2-EEPROM_A1)") (class "Default")
      (node (ref "J2") (pin "34") (pinfunction "EEPROM_A1_34") (pintype "bidirectional"))
      (node (ref "U2") (pin "2") (pinfunction "A1_2") (pintype "bidirectional"))
    )
    (net (code "31") (name "Net-(J2-EEPROM_A2)") (class "Default")
      (node (ref "J2") (pin "32") (pinfunction "EEPROM_A2_32") (pintype "bidirectional"))
      (node (ref "U2") (pin "3") (pinfunction "A2_3") (pintype "bidirectional"))
    )
    (net (code "32") (name "Net-(LED-0-Pad1)") (class "Default")
      (node (ref "LED-0") (pin "1") (pinfunction "1_1") (pintype "passive"))
      (node (ref "LED_0") (pin "C") (pinfunction "C_C") (pintype "passive"))
      (node (ref "R17") (pin "1") (pinfunction "1_1") (pintype "passive"))
    )
    (net (code "33") (name "Net-(LED-1-Pad1)") (class "Default")
      (node (ref "LED-1") (pin "1") (pinfunction "1_1") (pintype "passive"))
      (node (ref "LED_1") (pin "C") (pinfunction "C_C") (pintype "passive"))
      (node (ref "R18") (pin "1") (pinfunction "1_1") (pintype "passive"))
    )
    (net (code "34") (name "Net-(LED-LINK-Pad1)") (class "Default")
      (node (ref "LED-LINK") (pin "1") (pinfunction "1_1") (pintype "passive"))
      (node (ref "LINK_ST") (pin "A") (pinfunction "A_A") (pintype "passive"))
      (node (ref "R19") (pin "1") (pinfunction "1_1") (pintype "passive"))
    )
    (net (code "35") (name "Net-(LED-PWR-Pad1)") (class "Default")
      (node (ref "LED-PWR") (pin "1") (pinfunction "1_1") (pintype "passive"))
      (node (ref "R9") (pin "2") (pinfunction "2_2") (pintype "passive"))
    )
    (net (code "36") (name "Net-(LED_0-PadA)") (class "Default")
      (node (ref "LED_0") (pin "A") (pinfunction "A_A") (pintype "passive"))
      (node (ref "R11") (pin "2") (pinfunction "2_2") (pintype "passive"))
    )
    (net (code "37") (name "Net-(LED_1-PadA)") (class "Default")
      (node (ref "LED_1") (pin "A") (pinfunction "A_A") (pintype "passive"))
      (node (ref "R20") (pin "2") (pinfunction "2_2") (pintype "passive"))
    )
    (net (code "38") (name "Net-(LINK_ST-PadC)") (class "Default")
      (node (ref "LINK_ST") (pin "C") (pinfunction "C_C") (pintype "passive"))
      (node (ref "R21") (pin "2") (pinfunction "2_2") (pintype "passive"))
    )
    (net (code "39") (name "Net-(MS_SEL-Pad2)") (class "Default")
      (node (ref "MS_SEL") (pin "2") (pinfunction "2_2") (pintype "passive"))
      (node (ref "R14") (pin "1") (pinfunction "1_1") (pintype "passive"))
    )
    (net (code "40") (name "Net-(PWR-PadA)") (class "Default")
      (node (ref "PWR") (pin "A") (pinfunction "A_A") (pintype "passive"))
      (node (ref "R9") (pin "1") (pinfunction "1_1") (pintype "passive"))
    )
    (net (code "41") (name "Net-(Q1-D)") (class "Default")
      (node (ref "Q1") (pin "3") (pinfunction "D_3") (pintype "bidirectional"))
      (node (ref "R26") (pin "1") (pinfunction "1_1") (pintype "passive"))
    )
    (net (code "42") (name "Net-(Q2-D)") (class "Default")
      (node (ref "MEAS") (pin "1") (pinfunction "1_1") (pintype "passive"))
      (node (ref "MEAS") (pin "3") (pinfunction "1_3") (pintype "passive"))
      (node (ref "Q2") (pin "3") (pinfunction "D_3") (pintype "bidirectional"))
    )
    (net (code "43") (name "Net-(Q2-G)") (class "Default")
      (node (ref "Q2") (pin "1") (pinfunction "G_1") (pintype "bidirectional"))
      (node (ref "R26") (pin "2") (pinfunction "2_2") (pintype "passive"))
      (node (ref "R7") (pin "1") (pinfunction "1_1") (pintype "passive"))
    )
    (net (code "44") (name "Net-(R12-Pad1)") (class "Default")
      (node (ref "R12") (pin "1") (pinfunction "1_1") (pintype "passive"))
      (node (ref "TX2P4") (pin "2") (pinfunction "2_2") (pintype "passive"))
    )
    (net (code "45") (name "Net-(R13-Pad1)") (class "Default")
      (node (ref "R13") (pin "1") (pinfunction "1_1") (pintype "passive"))
      (node (ref "SWPD") (pin "2") (pinfunction "2_2") (pintype "passive"))
    )
    (net (code "46") (name "Net-(R15-Pad1)") (class "Default")
      (node (ref "R15") (pin "1") (pinfunction "1_1") (pintype "passive"))
      (node (ref "SPI_CFG1") (pin "2") (pinfunction "2_2") (pintype "passive"))
    )
    (net (code "47") (name "Net-(R16-Pad1)") (class "Default")
      (node (ref "R16") (pin "1") (pinfunction "1_1") (pintype "passive"))
      (node (ref "SPI_CFG0") (pin "2") (pinfunction "2_2") (pintype "passive"))
    )
    (net (code "48") (name "Net-(S1-2)") (class "Default")
      (node (ref "R27") (pin "2") (pinfunction "2_2") (pintype "passive"))
      (node (ref "R28") (pin "1") (pinfunction "1_1") (pintype "passive"))
      (node (ref "R29") (pin "2") (pinfunction "2_2") (pintype "passive"))
      (node (ref "S1") (pin "3") (pinfunction "2_3") (pintype "passive"))
    )
    (net (code "49") (name "Net-(U1-CEXT_2)") (class "Default")
      (node (ref "C18") (pin "1") (pinfunction "1_1") (pintype "passive"))
      (node (ref "U1") (pin "19") (pinfunction "CEXT_2_19") (pintype "bidirectional"))
    )
    (net (code "50") (name "Net-(U1-CEXT_3)") (class "Default")
      (node (ref "C19") (pin "1") (pinfunction "1_1") (pintype "passive"))
      (node (ref "U1") (pin "20") (pinfunction "CEXT_3_20") (pintype "bidirectional"))
    )
    (net (code "51") (name "Net-(U1-RXN)") (class "Default")
      (node (ref "R4") (pin "2") (pinfunction "2_2") (pintype "passive"))
      (node (ref "R6") (pin "2") (pinfunction "2_2") (pintype "passive"))
      (node (ref "U1") (pin "13") (pinfunction "RXN_13") (pintype "bidirectional"))
    )
    (net (code "52") (name "Net-(U1-RXP)") (class "Default")
      (node (ref "R3") (pin "1") (pinfunction "1_1") (pintype "passive"))
      (node (ref "R5") (pin "1") (pinfunction "1_1") (pintype "passive"))
      (node (ref "U1") (pin "14") (pinfunction "RXP_14") (pintype "bidirectional"))
    )
    (net (code "53") (name "Net-(U1-TEST1)") (class "Default")
      (node (ref "R10") (pin "1") (pinfunction "1_1") (pintype "passive"))
      (node (ref "U1") (pin "26") (pinfunction "TEST1_26") (pintype "bidirectional"))
    )
    (net (code "54") (name "Net-(U1-TXN)") (class "Default")
      (node (ref "R2") (pin "2") (pinfunction "2_2") (pintype "passive"))
      (node (ref "R5") (pin "2") (pinfunction "2_2") (pintype "passive"))
      (node (ref "U1") (pin "12") (pinfunction "TXN_12") (pintype "bidirectional"))
    )
    (net (code "55") (name "Net-(U1-TXP)") (class "Default")
      (node (ref "R1") (pin "2") (pinfunction "2_2") (pintype "passive"))
      (node (ref "R6") (pin "1") (pinfunction "1_1") (pintype "passive"))
      (node (ref "U1") (pin "15") (pinfunction "TXP_15") (pintype "bidirectional"))
    )
    (net (code "56") (name "Net-(U1-XTAL_I{slash}CLK_IN)") (class "Default")
      (node (ref "C5") (pin "1") (pinfunction "1_1") (pintype "passive"))
      (node (ref "U1") (pin "8") (pinfunction "XTAL_I/CLK_IN_8") (pintype "bidirectional"))
      (node (ref "Y1") (pin "1") (pinfunction "1_1") (pintype "passive"))
    )
    (net (code "57") (name "Net-(U1-XTAL_O)") (class "Default")
      (node (ref "C6") (pin "1") (pinfunction "1_1") (pintype "passive"))
      (node (ref "U1") (pin "9") (pinfunction "XTAL_O_9") (pintype "bidirectional"))
      (node (ref "Y1") (pin "3") (pinfunction "2_3") (pintype "passive"))
    )
    (net (code "58") (name "Net-(U1-~{RESET})") (class "Default")
      (node (ref "C23") (pin "1") (pinfunction "1_1") (pintype "passive"))
      (node (ref "R27") (pin "1") (pinfunction "1_1") (pintype "passive"))
      (node (ref "U1") (pin "5") (pinfunction "~{RESET}_5") (pintype "bidirectional"))
    )
    (net (code "59") (name "Net-(U3-IN)") (class "Default")
      (node (ref "C3") (pin "1") (pinfunction "1_1") (pintype "passive"))
      (node (ref "C8") (pin "1") (pinfunction "1_1") (pintype "passive"))
      (node (ref "MEAS") (pin "2") (pinfunction "2_2") (pintype "passive"))
      (node (ref "MEAS") (pin "4") (pinfunction "2_4") (pintype "passive"))
      (node (ref "U3") (pin "1") (pinfunction "IN_1") (pintype "input"))
    )
    (net (code "60") (name "PWR_EN") (class "Default")
      (node (ref "J2") (pin "71") (pinfunction "PWR_EN_71") (pintype "bidirectional"))
      (node (ref "Q1") (pin "1") (pinfunction "G_1") (pintype "bidirectional"))
      (node (ref "R22") (pin "2") (pinfunction "2_2") (pintype "passive"))
      (node (ref "U3") (pin "3") (pinfunction "EN_3") (pintype "input"))
    )
    (net (code "61") (name "SPI_CFG1") (class "Default")
      (node (ref "SPI_CFG1") (pin "1") (pinfunction "1_1") (pintype "passive"))
      (node (ref "U1") (pin "37") (pinfunction "SPI_CFG1_37") (pintype "bidirectional"))
    )
    (net (code "62") (name "SPI_PICO") (class "Default")
      (node (ref "COPI") (pin "1") (pinfunction "1_1") (pintype "bidirectional"))
      (node (ref "J2") (pin "5") (pinfunction "SPI_SDI_5") (pintype "bidirectional"))
      (node (ref "U1") (pin "1") (pinfunction "SDI_1") (pintype "bidirectional"))
    )
    (net (code "63") (name "SPI_POCI{slash}SPI_CFG0") (class "Default")
      (node (ref "CIPO") (pin "1") (pinfunction "1_1") (pintype "bidirectional"))
      (node (ref "J2") (pin "7") (pinfunction "SPI_SDO_7") (pintype "bidirectional"))
      (node (ref "SPI_CFG0") (pin "1") (pinfunction "1_1") (pintype "passive"))
      (node (ref "U1") (pin "2") (pinfunction "SDO/SPI_CFG0_2") (pintype "bidirectional"))
    )
    (net (code "64") (name "SPI_SCK") (class "Default")
      (node (ref "J2") (pin "3") (pinfunction "SPI_SCK_3") (pintype "bidirectional"))
      (node (ref "SPI") (pin "1") (pinfunction "1_1") (pintype "bidirectional"))
      (node (ref "U1") (pin "38") (pinfunction "SCLK_38") (pintype "bidirectional"))
    )
    (net (code "65") (name "VCC_IN") (class "Default")
      (node (ref "J2") (pin "72") (pinfunction "VCC_72") (pintype "bidirectional"))
      (node (ref "J2") (pin "74") (pinfunction "VCC_74") (pintype "bidirectional"))
      (node (ref "Q2") (pin "2") (pinfunction "S_2") (pintype "bidirectional"))
      (node (ref "R7") (pin "2") (pinfunction "2_2") (pintype "passive"))
    )
    (net (code "66") (name "unconnected-(J2-A0-Pad38)") (class "Default")
      (node (ref "J2") (pin "38") (pinfunction "A0_38") (pintype "bidirectional"))
    )
    (net (code "67") (name "unconnected-(J2-AUX_RX-Pad4)") (class "Default")
      (node (ref "J2") (pin "4") (pinfunction "AUX_RX_4") (pintype "bidirectional"))
    )
    (net (code "68") (name "unconnected-(J2-AUX_TX-Pad6)") (class "Default")
      (node (ref "J2") (pin "6") (pinfunction "AUX_TX_6") (pintype "bidirectional"))
    )
    (net (code "69") (name "unconnected-(J2-CAN-RX-Pad41)") (class "Default")
      (node (ref "J2") (pin "41") (pinfunction "CAN-RX_41") (pintype "bidirectional"))
    )
    (net (code "70") (name "unconnected-(J2-CAN-TX-Pad43)") (class "Default")
      (node (ref "J2") (pin "43") (pinfunction "CAN-TX_43") (pintype "bidirectional"))
    )
    (net (code "71") (name "unconnected-(J2-CTS-Pad18)") (class "Default")
      (node (ref "J2") (pin "18") (pinfunction "CTS_18") (pintype "bidirectional"))
    )
    (net (code "72") (name "unconnected-(J2-F2{slash}PWM-Pad51)") (class "Default")
      (node (ref "J2") (pin "51") (pinfunction "F2/PWM_51") (pintype "bidirectional"))
    )
    (net (code "73") (name "unconnected-(J2-F3-Pad53)") (class "Default")
      (node (ref "J2") (pin "53") (pinfunction "F3_53") (pintype "bidirectional"))
    )
    (net (code "74") (name "unconnected-(J2-F4-Pad55)") (class "Default")
      (node (ref "J2") (pin "55") (pinfunction "F4_55") (pintype "bidirectional"))
    )
    (net (code "75") (name "unconnected-(J2-F6-Pad59)") (class "Default")
      (node (ref "J2") (pin "59") (pinfunction "F6_59") (pintype "bidirectional"))
    )
    (net (code "76") (name "unconnected-(J2-F7-Pad61)") (class "Default")
      (node (ref "J2") (pin "61") (pinfunction "F7_61") (pintype "bidirectional"))
    )
    (net (code "77") (name "unconnected-(J2-I2C_~{INT}-Pad23)") (class "Default")
      (node (ref "J2") (pin "23") (pinfunction "I2C_~{INT}_23") (pintype "bidirectional"))
    )
    (net (code "78") (name "unconnected-(J2-MCU_~{BOOT}-Pad66)") (class "Default")
      (node (ref "J2") (pin "66") (pinfunction "MCU_~{BOOT}_66") (pintype "bidirectional"))
    )
    (net (code "79") (name "unconnected-(J2-MCU_~{RST}-Pad68)") (class "Default")
      (node (ref "J2") (pin "68") (pinfunction "MCU_~{RST}_68") (pintype "bidirectional"))
    )
    (net (code "80") (name "unconnected-(J2-RTS-Pad16)") (class "Default")
      (node (ref "J2") (pin "16") (pinfunction "RTS_16") (pintype "bidirectional"))
    )
    (net (code "81") (name "unconnected-(J2-RX-Pad15)") (class "Default")
      (node (ref "J2") (pin "15") (pinfunction "RX_15") (pintype "bidirectional"))
    )
    (net (code "82") (name "unconnected-(J2-TX-Pad13)") (class "Default")
      (node (ref "J2") (pin "13") (pinfunction "TX_13") (pintype "bidirectional"))
    )
    (net (code "83") (name "unconnected-(J2-USBHOST_D+-Pad35)") (class "Default")
      (node (ref "J2") (pin "35") (pinfunction "USBHOST_D+_35") (pintype "bidirectional"))
    )
    (net (code "84") (name "unconnected-(J2-USBHOST_D--Pad37)") (class "Default")
      (node (ref "J2") (pin "37") (pinfunction "USBHOST_D-_37") (pintype "bidirectional"))
    )
    (net (code "85") (name "unconnected-(J2-USB_VIN-Pad70)") (class "Default")
      (node (ref "J2") (pin "70") (pinfunction "USB_VIN_70") (pintype "bidirectional"))
    )
    (net (code "86") (name "unconnected-(U1-CLK25_REF-Pad7)") (class "Default")
      (node (ref "U1") (pin "7") (pinfunction "CLK25_REF_7") (pintype "bidirectional"))
    )
    (net (code "87") (name "unconnected-(U1-NC-Pad10)") (class "Default")
      (node (ref "U1") (pin "10") (pinfunction "NC_10") (pintype "no_connect"))
    )
    (net (code "88") (name "unconnected-(U1-NC-Pad11)") (class "Default")
      (node (ref "U1") (pin "11") (pinfunction "NC_11") (pintype "no_connect"))
    )
    (net (code "89") (name "unconnected-(U1-NC-Pad18)") (class "Default")
      (node (ref "U1") (pin "18") (pinfunction "NC_18") (pintype "no_connect"))
    )
    (net (code "90") (name "unconnected-(U1-NC-Pad21)") (class "Default")
      (node (ref "U1") (pin "21") (pinfunction "NC_21") (pintype "no_connect"))
    )
    (net (code "91") (name "unconnected-(U1-NC-Pad28)") (class "Default")
      (node (ref "U1") (pin "28") (pinfunction "NC_28") (pintype "no_connect"))
    )
    (net (code "92") (name "unconnected-(U1-NC-Pad32)") (class "Default")
      (node (ref "U1") (pin "32") (pinfunction "NC_32") (pintype "no_connect"))
    )
    (net (code "93") (name "unconnected-(U1-NC-Pad34)") (class "Default")
      (node (ref "U1") (pin "34") (pinfunction "NC_34") (pintype "no_connect"))
    )
    (net (code "94") (name "unconnected-(U1-NC-Pad36)") (class "Default")
      (node (ref "U1") (pin "36") (pinfunction "NC_36") (pintype "no_connect"))
    )
    (net (code "95") (name "unconnected-(U1-NC-Pad39)") (class "Default")
      (node (ref "U1") (pin "39") (pinfunction "NC_39") (pintype "no_connect"))
    )
    (net (code "96") (name "unconnected-(U1-TEST2-Pad27)") (class "Default")
      (node (ref "U1") (pin "27") (pinfunction "TEST2_27") (pintype "bidirectional"))
    )
    (net (code "97") (name "unconnected-(U1-TS_CAPT-Pad40)") (class "Default")
      (node (ref "U1") (pin "40") (pinfunction "TS_CAPT_40") (pintype "bidirectional"))
    )
  )
)
